# PA_LPF.net
KiCad netlist of a schematic drawn in Altium Designer
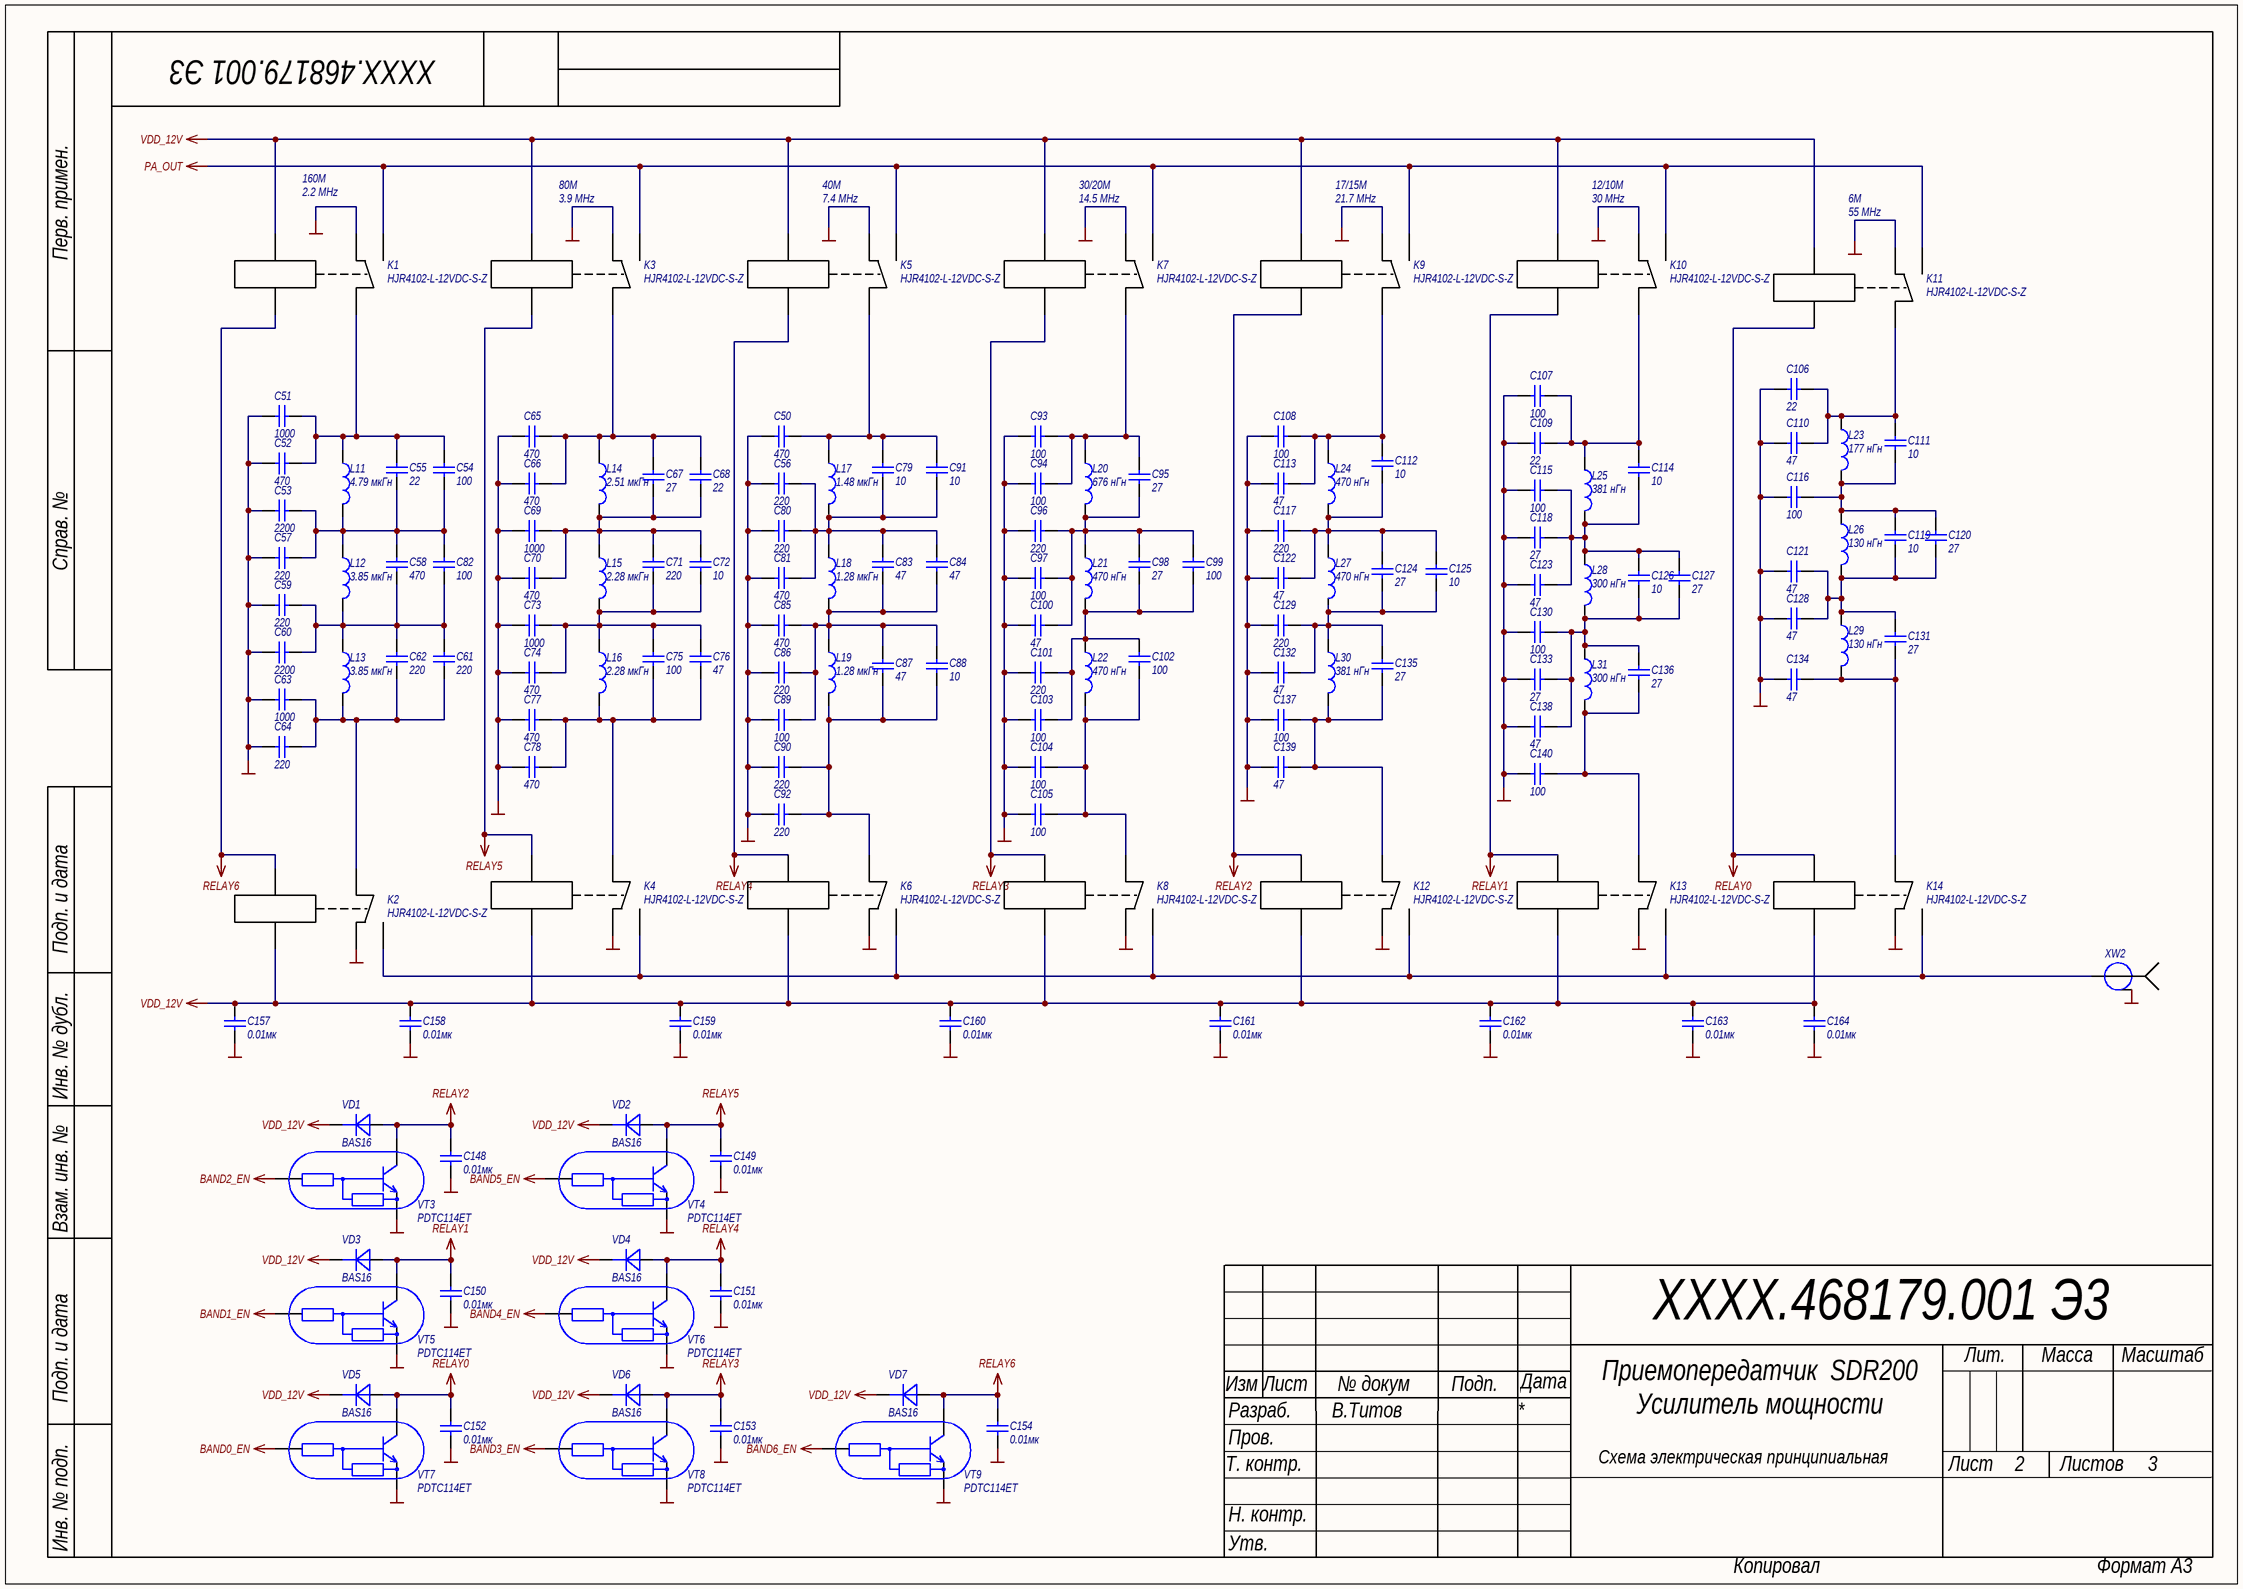
[diagram p0: PA_LPF.SchDoc]

(export (version "E")
  (design (tool "Eeschema 10.0.6"))
  (components
    (comp (ref "C50")
      (value "470")
      (footprint "CAPC3216X19L")
      (description "Кер. ЧИП-конденсатор")
      (fields (field (name "MANUFACTURER") "WALSIN") (field (name "TOLERANCE") "±10%"))
      (libsource (lib "nels_caps") (part "Кер.ЧИП конд. 1206 470пФ NP0 10% 2000В"))
    )
    (comp (ref "C51")
      (value "1000")
      (footprint "CAPC3216X19L")
      (description "Кер. ЧИП-конденсатор")
      (fields (field (name "MANUFACTURER") "Johanson") (field (name "TOLERANCE") "±10%"))
      (libsource (lib "nels_caps") (part "Кер.ЧИП конд. 1206 1000пФ X7К 10% 2000В"))
    )
    (comp (ref "C52")
      (value "470")
      (footprint "CAPC3216X19L")
      (description "Кер. ЧИП-конденсатор")
      (fields (field (name "MANUFACTURER") "WALSIN") (field (name "TOLERANCE") "±10%"))
      (libsource (lib "nels_caps") (part "Кер.ЧИП конд. 1206 470пФ NP0 10% 2000В"))
    )
    (comp (ref "C53")
      (value "2200")
      (footprint "CAPC3216X19L")
      (description "Кер. ЧИП-конденсатор")
      (fields (field (name "MANUFACTURER") "WALSIN") (field (name "TOLERANCE") "±10%"))
      (libsource (lib "nels_caps") (part "Кер.ЧИП конд. 1206 2200пФ X7К 10% 1000В"))
    )
    (comp (ref "C54")
      (value "100")
      (footprint "CAPC3216X19L")
      (description "Кер. ЧИП-конденсатор")
      (fields (field (name "MANUFACTURER") "WALSIN") (field (name "TOLERANCE") "±5%"))
      (libsource (lib "nels_caps") (part "Кер.ЧИП конд. 1206 100пФ NP0 5% 2000В"))
    )
    (comp (ref "C55")
      (value "22")
      (footprint "CAPC3216X19L")
      (description "Кер. ЧИП-конденсатор")
      (fields (field (name "MANUFACTURER") "WALSIN") (field (name "TOLERANCE") "±5%"))
      (libsource (lib "nels_caps") (part "Кер.ЧИП конд. 1206 22пФ NP0 5% 2000В"))
    )
    (comp (ref "C56")
      (value "220")
      (footprint "CAPC3216X19L")
      (description "Кер. ЧИП-конденсатор")
      (fields (field (name "MANUFACTURER") "Johanson") (field (name "TOLERANCE") "±10%"))
      (libsource (lib "nels_caps") (part "Кер.ЧИП конд. 1206 220пФ NP0 5% 2000В"))
    )
    (comp (ref "C57")
      (value "220")
      (footprint "CAPC3216X19L")
      (description "Кер. ЧИП-конденсатор")
      (fields (field (name "MANUFACTURER") "Johanson") (field (name "TOLERANCE") "±10%"))
      (libsource (lib "nels_caps") (part "Кер.ЧИП конд. 1206 220пФ NP0 5% 2000В"))
    )
    (comp (ref "C58")
      (value "470")
      (footprint "CAPC3216X19L")
      (description "Кер. ЧИП-конденсатор")
      (fields (field (name "MANUFACTURER") "WALSIN") (field (name "TOLERANCE") "±10%"))
      (libsource (lib "nels_caps") (part "Кер.ЧИП конд. 1206 470пФ NP0 10% 2000В"))
    )
    (comp (ref "C59")
      (value "220")
      (footprint "CAPC3216X19L")
      (description "Кер. ЧИП-конденсатор")
      (fields (field (name "MANUFACTURER") "Johanson") (field (name "TOLERANCE") "±10%"))
      (libsource (lib "nels_caps") (part "Кер.ЧИП конд. 1206 220пФ NP0 5% 2000В"))
    )
    (comp (ref "C60")
      (value "2200")
      (footprint "CAPC3216X19L")
      (description "Кер. ЧИП-конденсатор")
      (fields (field (name "MANUFACTURER") "WALSIN") (field (name "TOLERANCE") "±10%"))
      (libsource (lib "nels_caps") (part "Кер.ЧИП конд. 1206 2200пФ X7К 10% 1000В"))
    )
    (comp (ref "C61")
      (value "220")
      (footprint "CAPC3216X19L")
      (description "Кер. ЧИП-конденсатор")
      (fields (field (name "MANUFACTURER") "Johanson") (field (name "TOLERANCE") "±10%"))
      (libsource (lib "nels_caps") (part "Кер.ЧИП конд. 1206 220пФ NP0 5% 2000В"))
    )
    (comp (ref "C62")
      (value "220")
      (footprint "CAPC3216X19L")
      (description "Кер. ЧИП-конденсатор")
      (fields (field (name "MANUFACTURER") "Johanson") (field (name "TOLERANCE") "±10%"))
      (libsource (lib "nels_caps") (part "Кер.ЧИП конд. 1206 220пФ NP0 5% 2000В"))
    )
    (comp (ref "C63")
      (value "1000")
      (footprint "CAPC3216X19L")
      (description "Кер. ЧИП-конденсатор")
      (fields (field (name "MANUFACTURER") "Johanson") (field (name "TOLERANCE") "±10%"))
      (libsource (lib "nels_caps") (part "Кер.ЧИП конд. 1206 1000пФ X7К 10% 2000В"))
    )
    (comp (ref "C64")
      (value "220")
      (footprint "CAPC3216X19L")
      (description "Кер. ЧИП-конденсатор")
      (fields (field (name "MANUFACTURER") "Johanson") (field (name "TOLERANCE") "±10%"))
      (libsource (lib "nels_caps") (part "Кер.ЧИП конд. 1206 220пФ NP0 5% 2000В"))
    )
    (comp (ref "C65")
      (value "470")
      (footprint "CAPC3216X19L")
      (description "Кер. ЧИП-конденсатор")
      (fields (field (name "MANUFACTURER") "WALSIN") (field (name "TOLERANCE") "±10%"))
      (libsource (lib "nels_caps") (part "Кер.ЧИП конд. 1206 470пФ NP0 10% 2000В"))
    )
    (comp (ref "C66")
      (value "470")
      (footprint "CAPC3216X19L")
      (description "Кер. ЧИП-конденсатор")
      (fields (field (name "MANUFACTURER") "WALSIN") (field (name "TOLERANCE") "±10%"))
      (libsource (lib "nels_caps") (part "Кер.ЧИП конд. 1206 470пФ NP0 10% 2000В"))
    )
    (comp (ref "C67")
      (value "27")
      (footprint "CAPC3216X19L")
      (description "Кер. ЧИП-конденсатор")
      (fields (field (name "MANUFACTURER") "WALSIN") (field (name "TOLERANCE") "±10%"))
      (libsource (lib "nels_caps") (part "Кер.ЧИП конд. 1206 27пФ NP0 10% 2000В"))
    )
    (comp (ref "C68")
      (value "22")
      (footprint "CAPC3216X19L")
      (description "Кер. ЧИП-конденсатор")
      (fields (field (name "MANUFACTURER") "WALSIN") (field (name "TOLERANCE") "±5%"))
      (libsource (lib "nels_caps") (part "Кер.ЧИП конд. 1206 22пФ NP0 5% 2000В"))
    )
    (comp (ref "C69")
      (value "1000")
      (footprint "CAPC3216X19L")
      (description "Кер. ЧИП-конденсатор")
      (fields (field (name "MANUFACTURER") "Johanson") (field (name "TOLERANCE") "±10%"))
      (libsource (lib "nels_caps") (part "Кер.ЧИП конд. 1206 1000пФ X7К 10% 2000В"))
    )
    (comp (ref "C70")
      (value "470")
      (footprint "CAPC3216X19L")
      (description "Кер. ЧИП-конденсатор")
      (fields (field (name "MANUFACTURER") "WALSIN") (field (name "TOLERANCE") "±10%"))
      (libsource (lib "nels_caps") (part "Кер.ЧИП конд. 1206 470пФ NP0 10% 2000В"))
    )
    (comp (ref "C71")
      (value "220")
      (footprint "CAPC3216X19L")
      (description "Кер. ЧИП-конденсатор")
      (fields (field (name "MANUFACTURER") "Johanson") (field (name "TOLERANCE") "±10%"))
      (libsource (lib "nels_caps") (part "Кер.ЧИП конд. 1206 220пФ NP0 5% 2000В"))
    )
    (comp (ref "C72")
      (value "10")
      (footprint "CAPC3216X19L")
      (description "Кер. ЧИП-конденсатор")
      (fields (field (name "MANUFACTURER") "WALSIN") (field (name "TOLERANCE") "±5%"))
      (libsource (lib "nels_caps") (part "Кер.ЧИП конд. 1206 10пФ NP0 5% 2000В"))
    )
    (comp (ref "C73")
      (value "1000")
      (footprint "CAPC3216X19L")
      (description "Кер. ЧИП-конденсатор")
      (fields (field (name "MANUFACTURER") "Johanson") (field (name "TOLERANCE") "±10%"))
      (libsource (lib "nels_caps") (part "Кер.ЧИП конд. 1206 1000пФ X7К 10% 2000В"))
    )
    (comp (ref "C74")
      (value "470")
      (footprint "CAPC3216X19L")
      (description "Кер. ЧИП-конденсатор")
      (fields (field (name "MANUFACTURER") "WALSIN") (field (name "TOLERANCE") "±10%"))
      (libsource (lib "nels_caps") (part "Кер.ЧИП конд. 1206 470пФ NP0 10% 2000В"))
    )
    (comp (ref "C75")
      (value "100")
      (footprint "CAPC3216X19L")
      (description "Кер. ЧИП-конденсатор")
      (fields (field (name "MANUFACTURER") "WALSIN") (field (name "TOLERANCE") "±5%"))
      (libsource (lib "nels_caps") (part "Кер.ЧИП конд. 1206 100пФ NP0 5% 2000В"))
    )
    (comp (ref "C76")
      (value "47")
      (footprint "CAPC3216X19L")
      (description "Кер. ЧИП-конденсатор")
      (fields (field (name "MANUFACTURER") "WALSIN") (field (name "TOLERANCE") "±5%"))
      (libsource (lib "nels_caps") (part "Кер.ЧИП конд. 1206 47пФ NP0 5% 2000В"))
    )
    (comp (ref "C77")
      (value "470")
      (footprint "CAPC3216X19L")
      (description "Кер. ЧИП-конденсатор")
      (fields (field (name "MANUFACTURER") "WALSIN") (field (name "TOLERANCE") "±10%"))
      (libsource (lib "nels_caps") (part "Кер.ЧИП конд. 1206 470пФ NP0 10% 2000В"))
    )
    (comp (ref "C78")
      (value "470")
      (footprint "CAPC3216X19L")
      (description "Кер. ЧИП-конденсатор")
      (fields (field (name "MANUFACTURER") "WALSIN") (field (name "TOLERANCE") "±10%"))
      (libsource (lib "nels_caps") (part "Кер.ЧИП конд. 1206 470пФ NP0 10% 2000В"))
    )
    (comp (ref "C79")
      (value "10")
      (footprint "CAPC3216X19L")
      (description "Кер. ЧИП-конденсатор")
      (fields (field (name "MANUFACTURER") "WALSIN") (field (name "TOLERANCE") "±5%"))
      (libsource (lib "nels_caps") (part "Кер.ЧИП конд. 1206 10пФ NP0 5% 2000В"))
    )
    (comp (ref "C80")
      (value "220")
      (footprint "CAPC3216X19L")
      (description "Кер. ЧИП-конденсатор")
      (fields (field (name "MANUFACTURER") "Johanson") (field (name "TOLERANCE") "±10%"))
      (libsource (lib "nels_caps") (part "Кер.ЧИП конд. 1206 220пФ NP0 5% 2000В"))
    )
    (comp (ref "C81")
      (value "470")
      (footprint "CAPC3216X19L")
      (description "Кер. ЧИП-конденсатор")
      (fields (field (name "MANUFACTURER") "WALSIN") (field (name "TOLERANCE") "±10%"))
      (libsource (lib "nels_caps") (part "Кер.ЧИП конд. 1206 470пФ NP0 10% 2000В"))
    )
    (comp (ref "C82")
      (value "100")
      (footprint "CAPC3216X19L")
      (description "Кер. ЧИП-конденсатор")
      (fields (field (name "MANUFACTURER") "WALSIN") (field (name "TOLERANCE") "±5%"))
      (libsource (lib "nels_caps") (part "Кер.ЧИП конд. 1206 100пФ NP0 5% 2000В"))
    )
    (comp (ref "C83")
      (value "47")
      (footprint "CAPC3216X19L")
      (description "Кер. ЧИП-конденсатор")
      (fields (field (name "MANUFACTURER") "WALSIN") (field (name "TOLERANCE") "±5%"))
      (libsource (lib "nels_caps") (part "Кер.ЧИП конд. 1206 47пФ NP0 5% 2000В"))
    )
    (comp (ref "C84")
      (value "47")
      (footprint "CAPC3216X19L")
      (description "Кер. ЧИП-конденсатор")
      (fields (field (name "MANUFACTURER") "WALSIN") (field (name "TOLERANCE") "±5%"))
      (libsource (lib "nels_caps") (part "Кер.ЧИП конд. 1206 47пФ NP0 5% 2000В"))
    )
    (comp (ref "C85")
      (value "470")
      (footprint "CAPC3216X19L")
      (description "Кер. ЧИП-конденсатор")
      (fields (field (name "MANUFACTURER") "WALSIN") (field (name "TOLERANCE") "±10%"))
      (libsource (lib "nels_caps") (part "Кер.ЧИП конд. 1206 470пФ NP0 10% 2000В"))
    )
    (comp (ref "C86")
      (value "220")
      (footprint "CAPC3216X19L")
      (description "Кер. ЧИП-конденсатор")
      (fields (field (name "MANUFACTURER") "Johanson") (field (name "TOLERANCE") "±10%"))
      (libsource (lib "nels_caps") (part "Кер.ЧИП конд. 1206 220пФ NP0 5% 2000В"))
    )
    (comp (ref "C87")
      (value "47")
      (footprint "CAPC3216X19L")
      (description "Кер. ЧИП-конденсатор")
      (fields (field (name "MANUFACTURER") "WALSIN") (field (name "TOLERANCE") "±5%"))
      (libsource (lib "nels_caps") (part "Кер.ЧИП конд. 1206 47пФ NP0 5% 2000В"))
    )
    (comp (ref "C88")
      (value "10")
      (footprint "CAPC3216X19L")
      (description "Кер. ЧИП-конденсатор")
      (fields (field (name "MANUFACTURER") "WALSIN") (field (name "TOLERANCE") "±5%"))
      (libsource (lib "nels_caps") (part "Кер.ЧИП конд. 1206 10пФ NP0 5% 2000В"))
    )
    (comp (ref "C89")
      (value "100")
      (footprint "CAPC3216X19L")
      (description "Кер. ЧИП-конденсатор")
      (fields (field (name "MANUFACTURER") "WALSIN") (field (name "TOLERANCE") "±5%"))
      (libsource (lib "nels_caps") (part "Кер.ЧИП конд. 1206 100пФ NP0 5% 2000В"))
    )
    (comp (ref "C90")
      (value "220")
      (footprint "CAPC3216X19L")
      (description "Кер. ЧИП-конденсатор")
      (fields (field (name "MANUFACTURER") "Johanson") (field (name "TOLERANCE") "±10%"))
      (libsource (lib "nels_caps") (part "Кер.ЧИП конд. 1206 220пФ NP0 5% 2000В"))
    )
    (comp (ref "C91")
      (value "10")
      (footprint "CAPC3216X19L")
      (description "Кер. ЧИП-конденсатор")
      (fields (field (name "MANUFACTURER") "WALSIN") (field (name "TOLERANCE") "±5%"))
      (libsource (lib "nels_caps") (part "Кер.ЧИП конд. 1206 10пФ NP0 5% 2000В"))
    )
    (comp (ref "C92")
      (value "220")
      (footprint "CAPC3216X19L")
      (description "Кер. ЧИП-конденсатор")
      (fields (field (name "MANUFACTURER") "Johanson") (field (name "TOLERANCE") "±10%"))
      (libsource (lib "nels_caps") (part "Кер.ЧИП конд. 1206 220пФ NP0 5% 2000В"))
    )
    (comp (ref "C93")
      (value "100")
      (footprint "CAPC3216X19L")
      (description "Кер. ЧИП-конденсатор")
      (fields (field (name "MANUFACTURER") "WALSIN") (field (name "TOLERANCE") "±5%"))
      (libsource (lib "nels_caps") (part "Кер.ЧИП конд. 1206 100пФ NP0 5% 2000В"))
    )
    (comp (ref "C94")
      (value "100")
      (footprint "CAPC3216X19L")
      (description "Кер. ЧИП-конденсатор")
      (fields (field (name "MANUFACTURER") "WALSIN") (field (name "TOLERANCE") "±5%"))
      (libsource (lib "nels_caps") (part "Кер.ЧИП конд. 1206 100пФ NP0 5% 2000В"))
    )
    (comp (ref "C95")
      (value "27")
      (footprint "CAPC3216X19L")
      (description "Кер. ЧИП-конденсатор")
      (fields (field (name "MANUFACTURER") "WALSIN") (field (name "TOLERANCE") "±10%"))
      (libsource (lib "nels_caps") (part "Кер.ЧИП конд. 1206 27пФ NP0 10% 2000В"))
    )
    (comp (ref "C96")
      (value "220")
      (footprint "CAPC3216X19L")
      (description "Кер. ЧИП-конденсатор")
      (fields (field (name "MANUFACTURER") "Johanson") (field (name "TOLERANCE") "±10%"))
      (libsource (lib "nels_caps") (part "Кер.ЧИП конд. 1206 220пФ NP0 5% 2000В"))
    )
    (comp (ref "C97")
      (value "100")
      (footprint "CAPC3216X19L")
      (description "Кер. ЧИП-конденсатор")
      (fields (field (name "MANUFACTURER") "WALSIN") (field (name "TOLERANCE") "±5%"))
      (libsource (lib "nels_caps") (part "Кер.ЧИП конд. 1206 100пФ NP0 5% 2000В"))
    )
    (comp (ref "C98")
      (value "27")
      (footprint "CAPC3216X19L")
      (description "Кер. ЧИП-конденсатор")
      (fields (field (name "MANUFACTURER") "WALSIN") (field (name "TOLERANCE") "±10%"))
      (libsource (lib "nels_caps") (part "Кер.ЧИП конд. 1206 27пФ NP0 10% 2000В"))
    )
    (comp (ref "C99")
      (value "100")
      (footprint "CAPC3216X19L")
      (description "Кер. ЧИП-конденсатор")
      (fields (field (name "MANUFACTURER") "WALSIN") (field (name "TOLERANCE") "±5%"))
      (libsource (lib "nels_caps") (part "Кер.ЧИП конд. 1206 100пФ NP0 5% 2000В"))
    )
    (comp (ref "C100")
      (value "47")
      (footprint "CAPC3216X19L")
      (description "Кер. ЧИП-конденсатор")
      (fields (field (name "MANUFACTURER") "WALSIN") (field (name "TOLERANCE") "±5%"))
      (libsource (lib "nels_caps") (part "Кер.ЧИП конд. 1206 47пФ NP0 5% 2000В"))
    )
    (comp (ref "C101")
      (value "220")
      (footprint "CAPC3216X19L")
      (description "Кер. ЧИП-конденсатор")
      (fields (field (name "MANUFACTURER") "Johanson") (field (name "TOLERANCE") "±10%"))
      (libsource (lib "nels_caps") (part "Кер.ЧИП конд. 1206 220пФ NP0 5% 2000В"))
    )
    (comp (ref "C102")
      (value "100")
      (footprint "CAPC3216X19L")
      (description "Кер. ЧИП-конденсатор")
      (fields (field (name "MANUFACTURER") "WALSIN") (field (name "TOLERANCE") "±5%"))
      (libsource (lib "nels_caps") (part "Кер.ЧИП конд. 1206 100пФ NP0 5% 2000В"))
    )
    (comp (ref "C103")
      (value "100")
      (footprint "CAPC3216X19L")
      (description "Кер. ЧИП-конденсатор")
      (fields (field (name "MANUFACTURER") "WALSIN") (field (name "TOLERANCE") "±5%"))
      (libsource (lib "nels_caps") (part "Кер.ЧИП конд. 1206 100пФ NP0 5% 2000В"))
    )
    (comp (ref "C104")
      (value "100")
      (footprint "CAPC3216X19L")
      (description "Кер. ЧИП-конденсатор")
      (fields (field (name "MANUFACTURER") "WALSIN") (field (name "TOLERANCE") "±5%"))
      (libsource (lib "nels_caps") (part "Кер.ЧИП конд. 1206 100пФ NP0 5% 2000В"))
    )
    (comp (ref "C105")
      (value "100")
      (footprint "CAPC3216X19L")
      (description "Кер. ЧИП-конденсатор")
      (fields (field (name "MANUFACTURER") "WALSIN") (field (name "TOLERANCE") "±5%"))
      (libsource (lib "nels_caps") (part "Кер.ЧИП конд. 1206 100пФ NP0 5% 2000В"))
    )
    (comp (ref "C106")
      (value "22")
      (footprint "CAPC3216X19L")
      (description "Кер. ЧИП-конденсатор")
      (fields (field (name "MANUFACTURER") "WALSIN") (field (name "TOLERANCE") "±5%"))
      (libsource (lib "nels_caps") (part "Кер.ЧИП конд. 1206 22пФ NP0 5% 2000В"))
    )
    (comp (ref "C107")
      (value "100")
      (footprint "CAPC3216X19L")
      (description "Кер. ЧИП-конденсатор")
      (fields (field (name "MANUFACTURER") "WALSIN") (field (name "TOLERANCE") "±5%"))
      (libsource (lib "nels_caps") (part "Кер.ЧИП конд. 1206 100пФ NP0 5% 2000В"))
    )
    (comp (ref "C108")
      (value "100")
      (footprint "CAPC3216X19L")
      (description "Кер. ЧИП-конденсатор")
      (fields (field (name "MANUFACTURER") "WALSIN") (field (name "TOLERANCE") "±5%"))
      (libsource (lib "nels_caps") (part "Кер.ЧИП конд. 1206 100пФ NP0 5% 2000В"))
    )
    (comp (ref "C109")
      (value "22")
      (footprint "CAPC3216X19L")
      (description "Кер. ЧИП-конденсатор")
      (fields (field (name "MANUFACTURER") "WALSIN") (field (name "TOLERANCE") "±5%"))
      (libsource (lib "nels_caps") (part "Кер.ЧИП конд. 1206 22пФ NP0 5% 2000В"))
    )
    (comp (ref "C110")
      (value "47")
      (footprint "CAPC3216X19L")
      (description "Кер. ЧИП-конденсатор")
      (fields (field (name "MANUFACTURER") "WALSIN") (field (name "TOLERANCE") "±5%"))
      (libsource (lib "nels_caps") (part "Кер.ЧИП конд. 1206 47пФ NP0 5% 2000В"))
    )
    (comp (ref "C111")
      (value "10")
      (footprint "CAPC3216X19L")
      (description "Кер. ЧИП-конденсатор")
      (fields (field (name "MANUFACTURER") "WALSIN") (field (name "TOLERANCE") "±5%"))
      (libsource (lib "nels_caps") (part "Кер.ЧИП конд. 1206 10пФ NP0 5% 2000В"))
    )
    (comp (ref "C112")
      (value "10")
      (footprint "CAPC3216X19L")
      (description "Кер. ЧИП-конденсатор")
      (fields (field (name "MANUFACTURER") "WALSIN") (field (name "TOLERANCE") "±5%"))
      (libsource (lib "nels_caps") (part "Кер.ЧИП конд. 1206 10пФ NP0 5% 2000В"))
    )
    (comp (ref "C113")
      (value "47")
      (footprint "CAPC3216X19L")
      (description "Кер. ЧИП-конденсатор")
      (fields (field (name "MANUFACTURER") "WALSIN") (field (name "TOLERANCE") "±5%"))
      (libsource (lib "nels_caps") (part "Кер.ЧИП конд. 1206 47пФ NP0 5% 2000В"))
    )
    (comp (ref "C114")
      (value "10")
      (footprint "CAPC3216X19L")
      (description "Кер. ЧИП-конденсатор")
      (fields (field (name "MANUFACTURER") "WALSIN") (field (name "TOLERANCE") "±5%"))
      (libsource (lib "nels_caps") (part "Кер.ЧИП конд. 1206 10пФ NP0 5% 2000В"))
    )
    (comp (ref "C115")
      (value "100")
      (footprint "CAPC3216X19L")
      (description "Кер. ЧИП-конденсатор")
      (fields (field (name "MANUFACTURER") "WALSIN") (field (name "TOLERANCE") "±5%"))
      (libsource (lib "nels_caps") (part "Кер.ЧИП конд. 1206 100пФ NP0 5% 2000В"))
    )
    (comp (ref "C116")
      (value "100")
      (footprint "CAPC3216X19L")
      (description "Кер. ЧИП-конденсатор")
      (fields (field (name "MANUFACTURER") "WALSIN") (field (name "TOLERANCE") "±5%"))
      (libsource (lib "nels_caps") (part "Кер.ЧИП конд. 1206 100пФ NP0 5% 2000В"))
    )
    (comp (ref "C117")
      (value "220")
      (footprint "CAPC3216X19L")
      (description "Кер. ЧИП-конденсатор")
      (fields (field (name "MANUFACTURER") "Johanson") (field (name "TOLERANCE") "±10%"))
      (libsource (lib "nels_caps") (part "Кер.ЧИП конд. 1206 220пФ NP0 5% 2000В"))
    )
    (comp (ref "C118")
      (value "27")
      (footprint "CAPC3216X19L")
      (description "Кер. ЧИП-конденсатор")
      (fields (field (name "MANUFACTURER") "WALSIN") (field (name "TOLERANCE") "±10%"))
      (libsource (lib "nels_caps") (part "Кер.ЧИП конд. 1206 27пФ NP0 10% 2000В"))
    )
    (comp (ref "C119")
      (value "10")
      (footprint "CAPC3216X19L")
      (description "Кер. ЧИП-конденсатор")
      (fields (field (name "MANUFACTURER") "WALSIN") (field (name "TOLERANCE") "±5%"))
      (libsource (lib "nels_caps") (part "Кер.ЧИП конд. 1206 10пФ NP0 5% 2000В"))
    )
    (comp (ref "C120")
      (value "27")
      (footprint "CAPC3216X19L")
      (description "Кер. ЧИП-конденсатор")
      (fields (field (name "MANUFACTURER") "WALSIN") (field (name "TOLERANCE") "±10%"))
      (libsource (lib "nels_caps") (part "Кер.ЧИП конд. 1206 27пФ NP0 10% 2000В"))
    )
    (comp (ref "C121")
      (value "47")
      (footprint "CAPC3216X19L")
      (description "Кер. ЧИП-конденсатор")
      (fields (field (name "MANUFACTURER") "WALSIN") (field (name "TOLERANCE") "±5%"))
      (libsource (lib "nels_caps") (part "Кер.ЧИП конд. 1206 47пФ NP0 5% 2000В"))
    )
    (comp (ref "C122")
      (value "47")
      (footprint "CAPC3216X19L")
      (description "Кер. ЧИП-конденсатор")
      (fields (field (name "MANUFACTURER") "WALSIN") (field (name "TOLERANCE") "±5%"))
      (libsource (lib "nels_caps") (part "Кер.ЧИП конд. 1206 47пФ NP0 5% 2000В"))
    )
    (comp (ref "C123")
      (value "47")
      (footprint "CAPC3216X19L")
      (description "Кер. ЧИП-конденсатор")
      (fields (field (name "MANUFACTURER") "WALSIN") (field (name "TOLERANCE") "±5%"))
      (libsource (lib "nels_caps") (part "Кер.ЧИП конд. 1206 47пФ NP0 5% 2000В"))
    )
    (comp (ref "C124")
      (value "27")
      (footprint "CAPC3216X19L")
      (description "Кер. ЧИП-конденсатор")
      (fields (field (name "MANUFACTURER") "WALSIN") (field (name "TOLERANCE") "±10%"))
      (libsource (lib "nels_caps") (part "Кер.ЧИП конд. 1206 27пФ NP0 10% 2000В"))
    )
    (comp (ref "C125")
      (value "10")
      (footprint "CAPC3216X19L")
      (description "Кер. ЧИП-конденсатор")
      (fields (field (name "MANUFACTURER") "WALSIN") (field (name "TOLERANCE") "±5%"))
      (libsource (lib "nels_caps") (part "Кер.ЧИП конд. 1206 10пФ NP0 5% 2000В"))
    )
    (comp (ref "C126")
      (value "10")
      (footprint "CAPC3216X19L")
      (description "Кер. ЧИП-конденсатор")
      (fields (field (name "MANUFACTURER") "WALSIN") (field (name "TOLERANCE") "±5%"))
      (libsource (lib "nels_caps") (part "Кер.ЧИП конд. 1206 10пФ NP0 5% 2000В"))
    )
    (comp (ref "C127")
      (value "27")
      (footprint "CAPC3216X19L")
      (description "Кер. ЧИП-конденсатор")
      (fields (field (name "MANUFACTURER") "WALSIN") (field (name "TOLERANCE") "±10%"))
      (libsource (lib "nels_caps") (part "Кер.ЧИП конд. 1206 27пФ NP0 10% 2000В"))
    )
    (comp (ref "C128")
      (value "47")
      (footprint "CAPC3216X19L")
      (description "Кер. ЧИП-конденсатор")
      (fields (field (name "MANUFACTURER") "WALSIN") (field (name "TOLERANCE") "±5%"))
      (libsource (lib "nels_caps") (part "Кер.ЧИП конд. 1206 47пФ NP0 5% 2000В"))
    )
    (comp (ref "C129")
      (value "220")
      (footprint "CAPC3216X19L")
      (description "Кер. ЧИП-конденсатор")
      (fields (field (name "MANUFACTURER") "Johanson") (field (name "TOLERANCE") "±10%"))
      (libsource (lib "nels_caps") (part "Кер.ЧИП конд. 1206 220пФ NP0 5% 2000В"))
    )
    (comp (ref "C130")
      (value "100")
      (footprint "CAPC3216X19L")
      (description "Кер. ЧИП-конденсатор")
      (fields (field (name "MANUFACTURER") "WALSIN") (field (name "TOLERANCE") "±5%"))
      (libsource (lib "nels_caps") (part "Кер.ЧИП конд. 1206 100пФ NP0 5% 2000В"))
    )
    (comp (ref "C131")
      (value "27")
      (footprint "CAPC3216X19L")
      (description "Кер. ЧИП-конденсатор")
      (fields (field (name "MANUFACTURER") "WALSIN") (field (name "TOLERANCE") "±10%"))
      (libsource (lib "nels_caps") (part "Кер.ЧИП конд. 1206 27пФ NP0 10% 2000В"))
    )
    (comp (ref "C132")
      (value "47")
      (footprint "CAPC3216X19L")
      (description "Кер. ЧИП-конденсатор")
      (fields (field (name "MANUFACTURER") "WALSIN") (field (name "TOLERANCE") "±5%"))
      (libsource (lib "nels_caps") (part "Кер.ЧИП конд. 1206 47пФ NP0 5% 2000В"))
    )
    (comp (ref "C133")
      (value "27")
      (footprint "CAPC3216X19L")
      (description "Кер. ЧИП-конденсатор")
      (fields (field (name "MANUFACTURER") "WALSIN") (field (name "TOLERANCE") "±10%"))
      (libsource (lib "nels_caps") (part "Кер.ЧИП конд. 1206 27пФ NP0 10% 2000В"))
    )
    (comp (ref "C134")
      (value "47")
      (footprint "CAPC3216X19L")
      (description "Кер. ЧИП-конденсатор")
      (fields (field (name "MANUFACTURER") "WALSIN") (field (name "TOLERANCE") "±5%"))
      (libsource (lib "nels_caps") (part "Кер.ЧИП конд. 1206 47пФ NP0 5% 2000В"))
    )
    (comp (ref "C135")
      (value "27")
      (footprint "CAPC3216X19L")
      (description "Кер. ЧИП-конденсатор")
      (fields (field (name "MANUFACTURER") "WALSIN") (field (name "TOLERANCE") "±10%"))
      (libsource (lib "nels_caps") (part "Кер.ЧИП конд. 1206 27пФ NP0 10% 2000В"))
    )
    (comp (ref "C136")
      (value "27")
      (footprint "CAPC3216X19L")
      (description "Кер. ЧИП-конденсатор")
      (fields (field (name "MANUFACTURER") "WALSIN") (field (name "TOLERANCE") "±10%"))
      (libsource (lib "nels_caps") (part "Кер.ЧИП конд. 1206 27пФ NP0 10% 2000В"))
    )
    (comp (ref "C137")
      (value "100")
      (footprint "CAPC3216X19L")
      (description "Кер. ЧИП-конденсатор")
      (fields (field (name "MANUFACTURER") "WALSIN") (field (name "TOLERANCE") "±5%"))
      (libsource (lib "nels_caps") (part "Кер.ЧИП конд. 1206 100пФ NP0 5% 2000В"))
    )
    (comp (ref "C138")
      (value "47")
      (footprint "CAPC3216X19L")
      (description "Кер. ЧИП-конденсатор")
      (fields (field (name "MANUFACTURER") "WALSIN") (field (name "TOLERANCE") "±5%"))
      (libsource (lib "nels_caps") (part "Кер.ЧИП конд. 1206 47пФ NP0 5% 2000В"))
    )
    (comp (ref "C139")
      (value "47")
      (footprint "CAPC3216X19L")
      (description "Кер. ЧИП-конденсатор")
      (fields (field (name "MANUFACTURER") "WALSIN") (field (name "TOLERANCE") "±5%"))
      (libsource (lib "nels_caps") (part "Кер.ЧИП конд. 1206 47пФ NP0 5% 2000В"))
    )
    (comp (ref "C140")
      (value "100")
      (footprint "CAPC3216X19L")
      (description "Кер. ЧИП-конденсатор")
      (fields (field (name "MANUFACTURER") "WALSIN") (field (name "TOLERANCE") "±5%"))
      (libsource (lib "nels_caps") (part "Кер.ЧИП конд. 1206 100пФ NP0 5% 2000В"))
    )
    (comp (ref "C148")
      (value "0.01мк")
      (footprint "CAPC1005X06N")
      (description "Кер. ЧИП-конденсатор")
      (fields (field (name "TOLERANCE") "±20%"))
      (libsource (lib "nels_caps") (part "Кер.ЧИП конд. 0402 0.01мкФ X7R 10%, 50В"))
    )
    (comp (ref "C149")
      (value "0.01мк")
      (footprint "CAPC1005X06N")
      (description "Кер. ЧИП-конденсатор")
      (fields (field (name "TOLERANCE") "±20%"))
      (libsource (lib "nels_caps") (part "Кер.ЧИП конд. 0402 0.01мкФ X7R 10%, 50В"))
    )
    (comp (ref "C150")
      (value "0.01мк")
      (footprint "CAPC1005X06N")
      (description "Кер. ЧИП-конденсатор")
      (fields (field (name "TOLERANCE") "±20%"))
      (libsource (lib "nels_caps") (part "Кер.ЧИП конд. 0402 0.01мкФ X7R 10%, 50В"))
    )
    (comp (ref "C151")
      (value "0.01мк")
      (footprint "CAPC1005X06N")
      (description "Кер. ЧИП-конденсатор")
      (fields (field (name "TOLERANCE") "±20%"))
      (libsource (lib "nels_caps") (part "Кер.ЧИП конд. 0402 0.01мкФ X7R 10%, 50В"))
    )
    (comp (ref "C152")
      (value "0.01мк")
      (footprint "CAPC1005X06N")
      (description "Кер. ЧИП-конденсатор")
      (fields (field (name "TOLERANCE") "±20%"))
      (libsource (lib "nels_caps") (part "Кер.ЧИП конд. 0402 0.01мкФ X7R 10%, 50В"))
    )
    (comp (ref "C153")
      (value "0.01мк")
      (footprint "CAPC1005X06N")
      (description "Кер. ЧИП-конденсатор")
      (fields (field (name "TOLERANCE") "±20%"))
      (libsource (lib "nels_caps") (part "Кер.ЧИП конд. 0402 0.01мкФ X7R 10%, 50В"))
    )
    (comp (ref "C154")
      (value "0.01мк")
      (footprint "CAPC1005X06N")
      (description "Кер. ЧИП-конденсатор")
      (fields (field (name "TOLERANCE") "±20%"))
      (libsource (lib "nels_caps") (part "Кер.ЧИП конд. 0402 0.01мкФ X7R 10%, 50В"))
    )
    (comp (ref "C157")
      (value "0.01мк")
      (footprint "CAPC1005X06N")
      (description "Кер. ЧИП-конденсатор")
      (fields (field (name "TOLERANCE") "±20%"))
      (libsource (lib "nels_caps") (part "Кер.ЧИП конд. 0402 0.01мкФ X7R 10%, 50В"))
    )
    (comp (ref "C158")
      (value "0.01мк")
      (footprint "CAPC1005X06N")
      (description "Кер. ЧИП-конденсатор")
      (fields (field (name "TOLERANCE") "±20%"))
      (libsource (lib "nels_caps") (part "Кер.ЧИП конд. 0402 0.01мкФ X7R 10%, 50В"))
    )
    (comp (ref "C159")
      (value "0.01мк")
      (footprint "CAPC1005X06N")
      (description "Кер. ЧИП-конденсатор")
      (fields (field (name "TOLERANCE") "±20%"))
      (libsource (lib "nels_caps") (part "Кер.ЧИП конд. 0402 0.01мкФ X7R 10%, 50В"))
    )
    (comp (ref "C160")
      (value "0.01мк")
      (footprint "CAPC1005X06N")
      (description "Кер. ЧИП-конденсатор")
      (fields (field (name "TOLERANCE") "±20%"))
      (libsource (lib "nels_caps") (part "Кер.ЧИП конд. 0402 0.01мкФ X7R 10%, 50В"))
    )
    (comp (ref "C161")
      (value "0.01мк")
      (footprint "CAPC1005X06N")
      (description "Кер. ЧИП-конденсатор")
      (fields (field (name "TOLERANCE") "±20%"))
      (libsource (lib "nels_caps") (part "Кер.ЧИП конд. 0402 0.01мкФ X7R 10%, 50В"))
    )
    (comp (ref "C162")
      (value "0.01мк")
      (footprint "CAPC1005X06N")
      (description "Кер. ЧИП-конденсатор")
      (fields (field (name "TOLERANCE") "±20%"))
      (libsource (lib "nels_caps") (part "Кер.ЧИП конд. 0402 0.01мкФ X7R 10%, 50В"))
    )
    (comp (ref "C163")
      (value "0.01мк")
      (footprint "CAPC1005X06N")
      (description "Кер. ЧИП-конденсатор")
      (fields (field (name "TOLERANCE") "±20%"))
      (libsource (lib "nels_caps") (part "Кер.ЧИП конд. 0402 0.01мкФ X7R 10%, 50В"))
    )
    (comp (ref "C164")
      (value "0.01мк")
      (footprint "CAPC1005X06N")
      (description "Кер. ЧИП-конденсатор")
      (fields (field (name "TOLERANCE") "±20%"))
      (libsource (lib "nels_caps") (part "Кер.ЧИП конд. 0402 0.01мкФ X7R 10%, 50В"))
    )
    (comp (ref "K1")
      (value "HJR4102-L-12VDC-S-Z")
      (footprint "HJR4102")
      (description "Реле 1пер. 12VDC, 1A/240VAC")
      (libsource (lib "nels_other") (part "Реле HJR4102-L-12VDC-S-Z"))
    )
    (comp (ref "K2")
      (value "HJR4102-L-12VDC-S-Z")
      (footprint "HJR4102")
      (description "Реле 1пер. 12VDC, 1A/240VAC")
      (libsource (lib "nels_other") (part "Реле HJR4102-L-12VDC-S-Z"))
    )
    (comp (ref "K3")
      (value "HJR4102-L-12VDC-S-Z")
      (footprint "HJR4102")
      (description "Реле 1пер. 12VDC, 1A/240VAC")
      (libsource (lib "nels_other") (part "Реле HJR4102-L-12VDC-S-Z"))
    )
    (comp (ref "K4")
      (value "HJR4102-L-12VDC-S-Z")
      (footprint "HJR4102")
      (description "Реле 1пер. 12VDC, 1A/240VAC")
      (libsource (lib "nels_other") (part "Реле HJR4102-L-12VDC-S-Z"))
    )
    (comp (ref "K5")
      (value "HJR4102-L-12VDC-S-Z")
      (footprint "HJR4102")
      (description "Реле 1пер. 12VDC, 1A/240VAC")
      (libsource (lib "nels_other") (part "Реле HJR4102-L-12VDC-S-Z"))
    )
    (comp (ref "K6")
      (value "HJR4102-L-12VDC-S-Z")
      (footprint "HJR4102")
      (description "Реле 1пер. 12VDC, 1A/240VAC")
      (libsource (lib "nels_other") (part "Реле HJR4102-L-12VDC-S-Z"))
    )
    (comp (ref "K7")
      (value "HJR4102-L-12VDC-S-Z")
      (footprint "HJR4102")
      (description "Реле 1пер. 12VDC, 1A/240VAC")
      (libsource (lib "nels_other") (part "Реле HJR4102-L-12VDC-S-Z"))
    )
    (comp (ref "K8")
      (value "HJR4102-L-12VDC-S-Z")
      (footprint "HJR4102")
      (description "Реле 1пер. 12VDC, 1A/240VAC")
      (libsource (lib "nels_other") (part "Реле HJR4102-L-12VDC-S-Z"))
    )
    (comp (ref "K9")
      (value "HJR4102-L-12VDC-S-Z")
      (footprint "HJR4102")
      (description "Реле 1пер. 12VDC, 1A/240VAC")
      (libsource (lib "nels_other") (part "Реле HJR4102-L-12VDC-S-Z"))
    )
    (comp (ref "K10")
      (value "HJR4102-L-12VDC-S-Z")
      (footprint "HJR4102")
      (description "Реле 1пер. 12VDC, 1A/240VAC")
      (libsource (lib "nels_other") (part "Реле HJR4102-L-12VDC-S-Z"))
    )
    (comp (ref "K11")
      (value "HJR4102-L-12VDC-S-Z")
      (footprint "HJR4102")
      (description "Реле 1пер. 12VDC, 1A/240VAC")
      (libsource (lib "nels_other") (part "Реле HJR4102-L-12VDC-S-Z"))
    )
    (comp (ref "K12")
      (value "HJR4102-L-12VDC-S-Z")
      (footprint "HJR4102")
      (description "Реле 1пер. 12VDC, 1A/240VAC")
      (libsource (lib "nels_other") (part "Реле HJR4102-L-12VDC-S-Z"))
    )
    (comp (ref "K13")
      (value "HJR4102-L-12VDC-S-Z")
      (footprint "HJR4102")
      (description "Реле 1пер. 12VDC, 1A/240VAC")
      (libsource (lib "nels_other") (part "Реле HJR4102-L-12VDC-S-Z"))
    )
    (comp (ref "K14")
      (value "HJR4102-L-12VDC-S-Z")
      (footprint "HJR4102")
      (description "Реле 1пер. 12VDC, 1A/240VAC")
      (libsource (lib "nels_other") (part "Реле HJR4102-L-12VDC-S-Z"))
    )
    (comp (ref "L11")
      (value "4.79 мкГн")
      (footprint "T68-2")
      (description "29 витков")
      (libsource (lib "nels_ind") (part "Индуктивность T68-2 4.79 мкГн"))
    )
    (comp (ref "L12")
      (value "3.85 мкГн")
      (footprint "T68-2")
      (description "26 витков")
      (libsource (lib "nels_ind") (part "Индуктивность T68-2 3.85 мкГн"))
    )
    (comp (ref "L13")
      (value "3.85 мкГн")
      (footprint "T68-2")
      (description "26 витков")
      (libsource (lib "nels_ind") (part "Индуктивность T68-2 3.85 мкГн"))
    )
    (comp (ref "L14")
      (value "2.51 мкГн")
      (footprint "T68-2")
      (description "21 виток")
      (libsource (lib "nels_ind") (part "Индуктивность T68-2 2.51 мкГн"))
    )
    (comp (ref "L15")
      (value "2.28 мкГн")
      (footprint "T68-2")
      (libsource (lib "nels_ind") (part "Индуктивность T68-2 2.28 мкГн"))
    )
    (comp (ref "L16")
      (value "2.28 мкГн")
      (footprint "T68-2")
      (libsource (lib "nels_ind") (part "Индуктивность T68-2 2.28 мкГн"))
    )
    (comp (ref "L17")
      (value "1.48 мкГн")
      (footprint "T68-2")
      (description "16 витков")
      (libsource (lib "nels_ind") (part "Индуктивность T68-2 1.48 мкГн"))
    )
    (comp (ref "L18")
      (value "1.28 мкГн")
      (footprint "T68-2")
      (description "16 витков")
      (libsource (lib "nels_ind") (part "Индуктивность T68-2 1.28 мкГн"))
    )
    (comp (ref "L19")
      (value "1.28 мкГн")
      (footprint "T68-2")
      (description "16 витков")
      (libsource (lib "nels_ind") (part "Индуктивность T68-2 1.28 мкГн"))
    )
    (comp (ref "L20")
      (value "676 нГн")
      (footprint "T68-6")
      (description "12 витков")
      (libsource (lib "nels_ind") (part "Индуктивность T68-6 676 нГн"))
    )
    (comp (ref "L21")
      (value "470 нГн")
      (footprint "T68-6")
      (description "10 витков")
      (libsource (lib "nels_ind") (part "Индуктивность T68-6 470 нГн"))
    )
    (comp (ref "L22")
      (value "470 нГн")
      (footprint "T68-6")
      (description "10 витков")
      (libsource (lib "nels_ind") (part "Индуктивность T68-6 470 нГн"))
    )
    (comp (ref "L23")
      (value "177 нГн")
      (footprint "COIL D11 W4 L6")
      (description "4 витка, диаметр 11мм, длина 6мм")
      (libsource (lib "nels_ind") (part "Индуктивность 177 нГн"))
    )
    (comp (ref "L24")
      (value "470 нГн")
      (footprint "T68-6")
      (description "10 витков")
      (libsource (lib "nels_ind") (part "Индуктивность T68-6 470 нГн"))
    )
    (comp (ref "L25")
      (value "381 нГн")
      (footprint "T68-6")
      (description "9 витков")
      (libsource (lib "nels_ind") (part "Индуктивность T68-6 381 нГн"))
    )
    (comp (ref "L26")
      (value "130 нГн")
      (footprint "COIL D11 W4 L10")
      (description "4 витка, диаметр 11мм, длина 10мм")
      (libsource (lib "nels_ind") (part "Индуктивность 130 нГн"))
    )
    (comp (ref "L27")
      (value "470 нГн")
      (footprint "T68-6")
      (description "10 витков")
      (libsource (lib "nels_ind") (part "Индуктивность T68-6 470 нГн"))
    )
    (comp (ref "L28")
      (value "300 нГн")
      (footprint "T68-6")
      (description "8 витков")
      (libsource (lib "nels_ind") (part "Индуктивность T68-6 300 нГн"))
    )
    (comp (ref "L29")
      (value "130 нГн")
      (footprint "COIL D11 W4 L10")
      (description "4 витка, диаметр 11мм, длина 10мм")
      (libsource (lib "nels_ind") (part "Индуктивность 130 нГн"))
    )
    (comp (ref "L30")
      (value "381 нГн")
      (footprint "T68-6")
      (description "9 витков")
      (libsource (lib "nels_ind") (part "Индуктивность T68-6 381 нГн"))
    )
    (comp (ref "L31")
      (value "300 нГн")
      (footprint "T68-6")
      (description "8 витков")
      (libsource (lib "nels_ind") (part "Индуктивность T68-6 300 нГн"))
    )
    (comp (ref "VD1")
      (value "BAS16")
      (footprint "SOT23_N")
      (description "High-speed switching diodes")
      (fields (field (name "MANUFACTURER") "Nexperia"))
      (libsource (lib "nels_other") (part "ЧИП диод BAS16"))
    )
    (comp (ref "VD2")
      (value "BAS16")
      (footprint "SOT23_N")
      (description "High-speed switching diodes")
      (fields (field (name "MANUFACTURER") "Nexperia"))
      (libsource (lib "nels_other") (part "ЧИП диод BAS16"))
    )
    (comp (ref "VD3")
      (value "BAS16")
      (footprint "SOT23_N")
      (description "High-speed switching diodes")
      (fields (field (name "MANUFACTURER") "Nexperia"))
      (libsource (lib "nels_other") (part "ЧИП диод BAS16"))
    )
    (comp (ref "VD4")
      (value "BAS16")
      (footprint "SOT23_N")
      (description "High-speed switching diodes")
      (fields (field (name "MANUFACTURER") "Nexperia"))
      (libsource (lib "nels_other") (part "ЧИП диод BAS16"))
    )
    (comp (ref "VD5")
      (value "BAS16")
      (footprint "SOT23_N")
      (description "High-speed switching diodes")
      (fields (field (name "MANUFACTURER") "Nexperia"))
      (libsource (lib "nels_other") (part "ЧИП диод BAS16"))
    )
    (comp (ref "VD6")
      (value "BAS16")
      (footprint "SOT23_N")
      (description "High-speed switching diodes")
      (fields (field (name "MANUFACTURER") "Nexperia"))
      (libsource (lib "nels_other") (part "ЧИП диод BAS16"))
    )
    (comp (ref "VD7")
      (value "BAS16")
      (footprint "SOT23_N")
      (description "High-speed switching diodes")
      (fields (field (name "MANUFACTURER") "Nexperia"))
      (libsource (lib "nels_other") (part "ЧИП диод BAS16"))
    )
    (comp (ref "VT3")
      (value "PDTC114ET")
      (footprint "SOT23_N")
      (description "NPN resistor-equipped transistors;  R1 = 10 k, R2 = 10")
      (libsource (lib "nels_other") (part "ЧИП транзистор PDTC114ET"))
    )
    (comp (ref "VT4")
      (value "PDTC114ET")
      (footprint "SOT23_N")
      (description "NPN resistor-equipped transistors;  R1 = 10 k, R2 = 10")
      (libsource (lib "nels_other") (part "ЧИП транзистор PDTC114ET"))
    )
    (comp (ref "VT5")
      (value "PDTC114ET")
      (footprint "SOT23_N")
      (description "NPN resistor-equipped transistors;  R1 = 10 k, R2 = 10")
      (libsource (lib "nels_other") (part "ЧИП транзистор PDTC114ET"))
    )
    (comp (ref "VT6")
      (value "PDTC114ET")
      (footprint "SOT23_N")
      (description "NPN resistor-equipped transistors;  R1 = 10 k, R2 = 10")
      (libsource (lib "nels_other") (part "ЧИП транзистор PDTC114ET"))
    )
    (comp (ref "VT7")
      (value "PDTC114ET")
      (footprint "SOT23_N")
      (description "NPN resistor-equipped transistors;  R1 = 10 k, R2 = 10")
      (libsource (lib "nels_other") (part "ЧИП транзистор PDTC114ET"))
    )
    (comp (ref "VT8")
      (value "PDTC114ET")
      (footprint "SOT23_N")
      (description "NPN resistor-equipped transistors;  R1 = 10 k, R2 = 10")
      (libsource (lib "nels_other") (part "ЧИП транзистор PDTC114ET"))
    )
    (comp (ref "VT9")
      (value "PDTC114ET")
      (footprint "SOT23_N")
      (description "NPN resistor-equipped transistors;  R1 = 10 k, R2 = 10")
      (libsource (lib "nels_other") (part "ЧИП транзистор PDTC114ET"))
    )
    (comp (ref "XW2")
      (value "SMA-JR")
      (footprint "SMA-JR")
      (description "SMA-JR Разъем SMA гнездо на плату, прямой угол")
      (libsource (lib "nels_conn") (part "Соединитель коаксиальный SMA-JR"))
    )
  )
  (nets
    (net (code "1") (name "BAND0_EN") (class "Default")
      (node (ref "VT7") (pin "1") (pinfunction "B_1") (pintype "passive"))
    )
    (net (code "2") (name "BAND1_EN") (class "Default")
      (node (ref "VT5") (pin "1") (pinfunction "B_1") (pintype "passive"))
    )
    (net (code "3") (name "BAND2_EN") (class "Default")
      (node (ref "VT3") (pin "1") (pinfunction "B_1") (pintype "passive"))
    )
    (net (code "4") (name "BAND3_EN") (class "Default")
      (node (ref "VT8") (pin "1") (pinfunction "B_1") (pintype "passive"))
    )
    (net (code "5") (name "BAND4_EN") (class "Default")
      (node (ref "VT6") (pin "1") (pinfunction "B_1") (pintype "passive"))
    )
    (net (code "6") (name "BAND5_EN") (class "Default")
      (node (ref "VT4") (pin "1") (pinfunction "B_1") (pintype "passive"))
    )
    (net (code "7") (name "BAND6_EN") (class "Default")
      (node (ref "VT9") (pin "1") (pinfunction "B_1") (pintype "passive"))
    )
    (net (code "8") (name "GND") (class "Default")
      (node (ref "C100") (pin "2") (pinfunction "2_2") (pintype "passive"))
      (node (ref "C101") (pin "2") (pinfunction "2_2") (pintype "passive"))
      (node (ref "C103") (pin "2") (pinfunction "2_2") (pintype "passive"))
      (node (ref "C104") (pin "2") (pinfunction "2_2") (pintype "passive"))
      (node (ref "C105") (pin "2") (pinfunction "2_2") (pintype "passive"))
      (node (ref "C106") (pin "2") (pinfunction "2_2") (pintype "passive"))
      (node (ref "C107") (pin "2") (pinfunction "2_2") (pintype "passive"))
      (node (ref "C108") (pin "2") (pinfunction "2_2") (pintype "passive"))
      (node (ref "C109") (pin "2") (pinfunction "2_2") (pintype "passive"))
      (node (ref "C110") (pin "2") (pinfunction "2_2") (pintype "passive"))
      (node (ref "C113") (pin "2") (pinfunction "2_2") (pintype "passive"))
      (node (ref "C115") (pin "2") (pinfunction "2_2") (pintype "passive"))
      (node (ref "C116") (pin "2") (pinfunction "2_2") (pintype "passive"))
      (node (ref "C117") (pin "2") (pinfunction "2_2") (pintype "passive"))
      (node (ref "C118") (pin "2") (pinfunction "2_2") (pintype "passive"))
      (node (ref "C121") (pin "2") (pinfunction "2_2") (pintype "passive"))
      (node (ref "C122") (pin "2") (pinfunction "2_2") (pintype "passive"))
      (node (ref "C123") (pin "2") (pinfunction "2_2") (pintype "passive"))
      (node (ref "C128") (pin "2") (pinfunction "2_2") (pintype "passive"))
      (node (ref "C129") (pin "2") (pinfunction "2_2") (pintype "passive"))
      (node (ref "C130") (pin "2") (pinfunction "2_2") (pintype "passive"))
      (node (ref "C132") (pin "2") (pinfunction "2_2") (pintype "passive"))
      (node (ref "C133") (pin "2") (pinfunction "2_2") (pintype "passive"))
      (node (ref "C134") (pin "2") (pinfunction "2_2") (pintype "passive"))
      (node (ref "C137") (pin "2") (pinfunction "2_2") (pintype "passive"))
      (node (ref "C138") (pin "2") (pinfunction "2_2") (pintype "passive"))
      (node (ref "C139") (pin "2") (pinfunction "2_2") (pintype "passive"))
      (node (ref "C140") (pin "2") (pinfunction "2_2") (pintype "passive"))
      (node (ref "C148") (pin "1") (pinfunction "1_1") (pintype "passive"))
      (node (ref "C149") (pin "1") (pinfunction "1_1") (pintype "passive"))
      (node (ref "C150") (pin "1") (pinfunction "1_1") (pintype "passive"))
      (node (ref "C151") (pin "1") (pinfunction "1_1") (pintype "passive"))
      (node (ref "C152") (pin "1") (pinfunction "1_1") (pintype "passive"))
      (node (ref "C153") (pin "1") (pinfunction "1_1") (pintype "passive"))
      (node (ref "C154") (pin "1") (pinfunction "1_1") (pintype "passive"))
      (node (ref "C157") (pin "1") (pinfunction "1_1") (pintype "passive"))
      (node (ref "C158") (pin "1") (pinfunction "1_1") (pintype "passive"))
      (node (ref "C159") (pin "1") (pinfunction "1_1") (pintype "passive"))
      (node (ref "C160") (pin "1") (pinfunction "1_1") (pintype "passive"))
      (node (ref "C161") (pin "1") (pinfunction "1_1") (pintype "passive"))
      (node (ref "C162") (pin "1") (pinfunction "1_1") (pintype "passive"))
      (node (ref "C163") (pin "1") (pinfunction "1_1") (pintype "passive"))
      (node (ref "C164") (pin "1") (pinfunction "1_1") (pintype "passive"))
      (node (ref "C50") (pin "2") (pinfunction "2_2") (pintype "passive"))
      (node (ref "C51") (pin "2") (pinfunction "2_2") (pintype "passive"))
      (node (ref "C52") (pin "2") (pinfunction "2_2") (pintype "passive"))
      (node (ref "C53") (pin "2") (pinfunction "2_2") (pintype "passive"))
      (node (ref "C56") (pin "2") (pinfunction "2_2") (pintype "passive"))
      (node (ref "C57") (pin "2") (pinfunction "2_2") (pintype "passive"))
      (node (ref "C59") (pin "2") (pinfunction "2_2") (pintype "passive"))
      (node (ref "C60") (pin "2") (pinfunction "2_2") (pintype "passive"))
      (node (ref "C63") (pin "2") (pinfunction "2_2") (pintype "passive"))
      (node (ref "C64") (pin "2") (pinfunction "2_2") (pintype "passive"))
      (node (ref "C65") (pin "2") (pinfunction "2_2") (pintype "passive"))
      (node (ref "C66") (pin "2") (pinfunction "2_2") (pintype "passive"))
      (node (ref "C69") (pin "2") (pinfunction "2_2") (pintype "passive"))
      (node (ref "C70") (pin "2") (pinfunction "2_2") (pintype "passive"))
      (node (ref "C73") (pin "2") (pinfunction "2_2") (pintype "passive"))
      (node (ref "C74") (pin "2") (pinfunction "2_2") (pintype "passive"))
      (node (ref "C77") (pin "2") (pinfunction "2_2") (pintype "passive"))
      (node (ref "C78") (pin "2") (pinfunction "2_2") (pintype "passive"))
      (node (ref "C80") (pin "2") (pinfunction "2_2") (pintype "passive"))
      (node (ref "C81") (pin "2") (pinfunction "2_2") (pintype "passive"))
      (node (ref "C85") (pin "2") (pinfunction "2_2") (pintype "passive"))
      (node (ref "C86") (pin "2") (pinfunction "2_2") (pintype "passive"))
      (node (ref "C89") (pin "2") (pinfunction "2_2") (pintype "passive"))
      (node (ref "C90") (pin "2") (pinfunction "2_2") (pintype "passive"))
      (node (ref "C92") (pin "2") (pinfunction "2_2") (pintype "passive"))
      (node (ref "C93") (pin "2") (pinfunction "2_2") (pintype "passive"))
      (node (ref "C94") (pin "2") (pinfunction "2_2") (pintype "passive"))
      (node (ref "C96") (pin "2") (pinfunction "2_2") (pintype "passive"))
      (node (ref "C97") (pin "2") (pinfunction "2_2") (pintype "passive"))
      (node (ref "K1") (pin "7") (pintype "passive"))
      (node (ref "K10") (pin "7") (pintype "passive"))
      (node (ref "K11") (pin "7") (pintype "passive"))
      (node (ref "K12") (pin "7") (pintype "passive"))
      (node (ref "K13") (pin "7") (pintype "passive"))
      (node (ref "K14") (pin "7") (pintype "passive"))
      (node (ref "K2") (pin "7") (pintype "passive"))
      (node (ref "K3") (pin "7") (pintype "passive"))
      (node (ref "K4") (pin "7") (pintype "passive"))
      (node (ref "K5") (pin "7") (pintype "passive"))
      (node (ref "K6") (pin "7") (pintype "passive"))
      (node (ref "K7") (pin "7") (pintype "passive"))
      (node (ref "K8") (pin "7") (pintype "passive"))
      (node (ref "K9") (pin "7") (pintype "passive"))
      (node (ref "VT3") (pin "2") (pinfunction "E_2") (pintype "passive"))
      (node (ref "VT4") (pin "2") (pinfunction "E_2") (pintype "passive"))
      (node (ref "VT5") (pin "2") (pinfunction "E_2") (pintype "passive"))
      (node (ref "VT6") (pin "2") (pinfunction "E_2") (pintype "passive"))
      (node (ref "VT7") (pin "2") (pinfunction "E_2") (pintype "passive"))
      (node (ref "VT8") (pin "2") (pinfunction "E_2") (pintype "passive"))
      (node (ref "VT9") (pin "2") (pinfunction "E_2") (pintype "passive"))
      (node (ref "XW2") (pin "2") (pinfunction "2_2") (pintype "passive"))
    )
    (net (code "9") (name "Net-(C50-Pad1)") (class "Default")
      (node (ref "C50") (pin "1") (pinfunction "1_1") (pintype "passive"))
      (node (ref "C79") (pin "2") (pinfunction "2_2") (pintype "passive"))
      (node (ref "C91") (pin "2") (pinfunction "2_2") (pintype "passive"))
      (node (ref "K5") (pin "12") (pintype "passive"))
      (node (ref "L17") (pin "1") (pinfunction "1_1") (pintype "passive"))
    )
    (net (code "10") (name "Net-(C51-Pad1)") (class "Default")
      (node (ref "C51") (pin "1") (pinfunction "1_1") (pintype "passive"))
      (node (ref "C52") (pin "1") (pinfunction "1_1") (pintype "passive"))
      (node (ref "C54") (pin "2") (pinfunction "2_2") (pintype "passive"))
      (node (ref "C55") (pin "2") (pinfunction "2_2") (pintype "passive"))
      (node (ref "K1") (pin "12") (pintype "passive"))
      (node (ref "L11") (pin "1") (pinfunction "1_1") (pintype "passive"))
    )
    (net (code "11") (name "Net-(C53-Pad1)") (class "Default")
      (node (ref "C53") (pin "1") (pinfunction "1_1") (pintype "passive"))
      (node (ref "C54") (pin "1") (pinfunction "1_1") (pintype "passive"))
      (node (ref "C55") (pin "1") (pinfunction "1_1") (pintype "passive"))
      (node (ref "C57") (pin "1") (pinfunction "1_1") (pintype "passive"))
      (node (ref "C58") (pin "2") (pinfunction "2_2") (pintype "passive"))
      (node (ref "C82") (pin "2") (pinfunction "2_2") (pintype "passive"))
      (node (ref "L11") (pin "2") (pinfunction "2_2") (pintype "passive"))
      (node (ref "L12") (pin "1") (pinfunction "1_1") (pintype "passive"))
    )
    (net (code "12") (name "Net-(C56-Pad1)") (class "Default")
      (node (ref "C56") (pin "1") (pinfunction "1_1") (pintype "passive"))
      (node (ref "C79") (pin "1") (pinfunction "1_1") (pintype "passive"))
      (node (ref "C80") (pin "1") (pinfunction "1_1") (pintype "passive"))
      (node (ref "C81") (pin "1") (pinfunction "1_1") (pintype "passive"))
      (node (ref "C83") (pin "2") (pinfunction "2_2") (pintype "passive"))
      (node (ref "C84") (pin "2") (pinfunction "2_2") (pintype "passive"))
      (node (ref "C91") (pin "1") (pinfunction "1_1") (pintype "passive"))
      (node (ref "L17") (pin "2") (pinfunction "2_2") (pintype "passive"))
      (node (ref "L18") (pin "1") (pinfunction "1_1") (pintype "passive"))
    )
    (net (code "13") (name "Net-(C58-Pad1)") (class "Default")
      (node (ref "C58") (pin "1") (pinfunction "1_1") (pintype "passive"))
      (node (ref "C59") (pin "1") (pinfunction "1_1") (pintype "passive"))
      (node (ref "C60") (pin "1") (pinfunction "1_1") (pintype "passive"))
      (node (ref "C61") (pin "2") (pinfunction "2_2") (pintype "passive"))
      (node (ref "C62") (pin "2") (pinfunction "2_2") (pintype "passive"))
      (node (ref "C82") (pin "1") (pinfunction "1_1") (pintype "passive"))
      (node (ref "L12") (pin "2") (pinfunction "2_2") (pintype "passive"))
      (node (ref "L13") (pin "1") (pinfunction "1_1") (pintype "passive"))
    )
    (net (code "14") (name "Net-(C61-Pad1)") (class "Default")
      (node (ref "C61") (pin "1") (pinfunction "1_1") (pintype "passive"))
      (node (ref "C62") (pin "1") (pinfunction "1_1") (pintype "passive"))
      (node (ref "C63") (pin "1") (pinfunction "1_1") (pintype "passive"))
      (node (ref "C64") (pin "1") (pinfunction "1_1") (pintype "passive"))
      (node (ref "K2") (pin "12") (pintype "passive"))
      (node (ref "L13") (pin "2") (pinfunction "2_2") (pintype "passive"))
    )
    (net (code "15") (name "Net-(C65-Pad1)") (class "Default")
      (node (ref "C65") (pin "1") (pinfunction "1_1") (pintype "passive"))
      (node (ref "C66") (pin "1") (pinfunction "1_1") (pintype "passive"))
      (node (ref "C67") (pin "2") (pinfunction "2_2") (pintype "passive"))
      (node (ref "C68") (pin "2") (pinfunction "2_2") (pintype "passive"))
      (node (ref "K3") (pin "12") (pintype "passive"))
      (node (ref "L14") (pin "1") (pinfunction "1_1") (pintype "passive"))
    )
    (net (code "16") (name "Net-(C67-Pad1)") (class "Default")
      (node (ref "C67") (pin "1") (pinfunction "1_1") (pintype "passive"))
      (node (ref "C68") (pin "1") (pinfunction "1_1") (pintype "passive"))
      (node (ref "C69") (pin "1") (pinfunction "1_1") (pintype "passive"))
      (node (ref "C70") (pin "1") (pinfunction "1_1") (pintype "passive"))
      (node (ref "C71") (pin "1") (pinfunction "1_1") (pintype "passive"))
      (node (ref "C72") (pin "2") (pinfunction "2_2") (pintype "passive"))
      (node (ref "L14") (pin "2") (pinfunction "2_2") (pintype "passive"))
      (node (ref "L15") (pin "1") (pinfunction "1_1") (pintype "passive"))
    )
    (net (code "17") (name "Net-(C71-Pad2)") (class "Default")
      (node (ref "C71") (pin "2") (pinfunction "2_2") (pintype "passive"))
      (node (ref "C72") (pin "1") (pinfunction "1_1") (pintype "passive"))
      (node (ref "C73") (pin "1") (pinfunction "1_1") (pintype "passive"))
      (node (ref "C74") (pin "1") (pinfunction "1_1") (pintype "passive"))
      (node (ref "C75") (pin "2") (pinfunction "2_2") (pintype "passive"))
      (node (ref "C76") (pin "2") (pinfunction "2_2") (pintype "passive"))
      (node (ref "L15") (pin "2") (pinfunction "2_2") (pintype "passive"))
      (node (ref "L16") (pin "1") (pinfunction "1_1") (pintype "passive"))
    )
    (net (code "18") (name "Net-(C75-Pad1)") (class "Default")
      (node (ref "C75") (pin "1") (pinfunction "1_1") (pintype "passive"))
      (node (ref "C76") (pin "1") (pinfunction "1_1") (pintype "passive"))
      (node (ref "C77") (pin "1") (pinfunction "1_1") (pintype "passive"))
      (node (ref "C78") (pin "1") (pinfunction "1_1") (pintype "passive"))
      (node (ref "K4") (pin "12") (pintype "passive"))
      (node (ref "L16") (pin "2") (pinfunction "2_2") (pintype "passive"))
    )
    (net (code "19") (name "Net-(C83-Pad1)") (class "Default")
      (node (ref "C83") (pin "1") (pinfunction "1_1") (pintype "passive"))
      (node (ref "C84") (pin "1") (pinfunction "1_1") (pintype "passive"))
      (node (ref "C85") (pin "1") (pinfunction "1_1") (pintype "passive"))
      (node (ref "C86") (pin "1") (pinfunction "1_1") (pintype "passive"))
      (node (ref "C87") (pin "2") (pinfunction "2_2") (pintype "passive"))
      (node (ref "C88") (pin "2") (pinfunction "2_2") (pintype "passive"))
      (node (ref "C89") (pin "1") (pinfunction "1_1") (pintype "passive"))
      (node (ref "L18") (pin "2") (pinfunction "2_2") (pintype "passive"))
      (node (ref "L19") (pin "1") (pinfunction "1_1") (pintype "passive"))
    )
    (net (code "20") (name "Net-(C87-Pad1)") (class "Default")
      (node (ref "C87") (pin "1") (pinfunction "1_1") (pintype "passive"))
      (node (ref "C88") (pin "1") (pinfunction "1_1") (pintype "passive"))
      (node (ref "C90") (pin "1") (pinfunction "1_1") (pintype "passive"))
      (node (ref "C92") (pin "1") (pinfunction "1_1") (pintype "passive"))
      (node (ref "K6") (pin "12") (pintype "passive"))
      (node (ref "L19") (pin "2") (pinfunction "2_2") (pintype "passive"))
    )
    (net (code "21") (name "Net-(C93-Pad1)") (class "Default")
      (node (ref "C93") (pin "1") (pinfunction "1_1") (pintype "passive"))
      (node (ref "C94") (pin "1") (pinfunction "1_1") (pintype "passive"))
      (node (ref "C95") (pin "2") (pinfunction "2_2") (pintype "passive"))
      (node (ref "K7") (pin "12") (pintype "passive"))
      (node (ref "L20") (pin "1") (pinfunction "1_1") (pintype "passive"))
    )
    (net (code "22") (name "Net-(C100-Pad1)") (class "Default")
      (node (ref "C100") (pin "1") (pinfunction "1_1") (pintype "passive"))
      (node (ref "C95") (pin "1") (pinfunction "1_1") (pintype "passive"))
      (node (ref "C96") (pin "1") (pinfunction "1_1") (pintype "passive"))
      (node (ref "C97") (pin "1") (pinfunction "1_1") (pintype "passive"))
      (node (ref "C98") (pin "2") (pinfunction "2_2") (pintype "passive"))
      (node (ref "C99") (pin "2") (pinfunction "2_2") (pintype "passive"))
      (node (ref "L20") (pin "2") (pinfunction "2_2") (pintype "passive"))
      (node (ref "L21") (pin "1") (pinfunction "1_1") (pintype "passive"))
    )
    (net (code "23") (name "Net-(C101-Pad1)") (class "Default")
      (node (ref "C101") (pin "1") (pinfunction "1_1") (pintype "passive"))
      (node (ref "C102") (pin "2") (pinfunction "2_2") (pintype "passive"))
      (node (ref "C103") (pin "1") (pinfunction "1_1") (pintype "passive"))
      (node (ref "C98") (pin "1") (pinfunction "1_1") (pintype "passive"))
      (node (ref "C99") (pin "1") (pinfunction "1_1") (pintype "passive"))
      (node (ref "L21") (pin "2") (pinfunction "2_2") (pintype "passive"))
      (node (ref "L22") (pin "1") (pinfunction "1_1") (pintype "passive"))
    )
    (net (code "24") (name "Net-(C102-Pad1)") (class "Default")
      (node (ref "C102") (pin "1") (pinfunction "1_1") (pintype "passive"))
      (node (ref "C104") (pin "1") (pinfunction "1_1") (pintype "passive"))
      (node (ref "C105") (pin "1") (pinfunction "1_1") (pintype "passive"))
      (node (ref "K8") (pin "12") (pintype "passive"))
      (node (ref "L22") (pin "2") (pinfunction "2_2") (pintype "passive"))
    )
    (net (code "25") (name "Net-(C106-Pad1)") (class "Default")
      (node (ref "C106") (pin "1") (pinfunction "1_1") (pintype "passive"))
      (node (ref "C110") (pin "1") (pinfunction "1_1") (pintype "passive"))
      (node (ref "C111") (pin "2") (pinfunction "2_2") (pintype "passive"))
      (node (ref "K11") (pin "12") (pintype "passive"))
      (node (ref "L23") (pin "1") (pinfunction "1_1") (pintype "passive"))
    )
    (net (code "26") (name "Net-(C107-Pad1)") (class "Default")
      (node (ref "C107") (pin "1") (pinfunction "1_1") (pintype "passive"))
      (node (ref "C109") (pin "1") (pinfunction "1_1") (pintype "passive"))
      (node (ref "C114") (pin "2") (pinfunction "2_2") (pintype "passive"))
      (node (ref "K10") (pin "12") (pintype "passive"))
      (node (ref "L25") (pin "1") (pinfunction "1_1") (pintype "passive"))
    )
    (net (code "27") (name "Net-(C108-Pad1)") (class "Default")
      (node (ref "C108") (pin "1") (pinfunction "1_1") (pintype "passive"))
      (node (ref "C112") (pin "2") (pinfunction "2_2") (pintype "passive"))
      (node (ref "C113") (pin "1") (pinfunction "1_1") (pintype "passive"))
      (node (ref "K9") (pin "12") (pintype "passive"))
      (node (ref "L24") (pin "1") (pinfunction "1_1") (pintype "passive"))
    )
    (net (code "28") (name "Net-(C111-Pad1)") (class "Default")
      (node (ref "C111") (pin "1") (pinfunction "1_1") (pintype "passive"))
      (node (ref "C116") (pin "1") (pinfunction "1_1") (pintype "passive"))
      (node (ref "C119") (pin "2") (pinfunction "2_2") (pintype "passive"))
      (node (ref "C120") (pin "2") (pinfunction "2_2") (pintype "passive"))
      (node (ref "L23") (pin "2") (pinfunction "2_2") (pintype "passive"))
      (node (ref "L26") (pin "1") (pinfunction "1_1") (pintype "passive"))
    )
    (net (code "29") (name "Net-(C112-Pad1)") (class "Default")
      (node (ref "C112") (pin "1") (pinfunction "1_1") (pintype "passive"))
      (node (ref "C117") (pin "1") (pinfunction "1_1") (pintype "passive"))
      (node (ref "C122") (pin "1") (pinfunction "1_1") (pintype "passive"))
      (node (ref "C124") (pin "2") (pinfunction "2_2") (pintype "passive"))
      (node (ref "C125") (pin "2") (pinfunction "2_2") (pintype "passive"))
      (node (ref "L24") (pin "2") (pinfunction "2_2") (pintype "passive"))
      (node (ref "L27") (pin "1") (pinfunction "1_1") (pintype "passive"))
    )
    (net (code "30") (name "Net-(C114-Pad1)") (class "Default")
      (node (ref "C114") (pin "1") (pinfunction "1_1") (pintype "passive"))
      (node (ref "C115") (pin "1") (pinfunction "1_1") (pintype "passive"))
      (node (ref "C118") (pin "1") (pinfunction "1_1") (pintype "passive"))
      (node (ref "C123") (pin "1") (pinfunction "1_1") (pintype "passive"))
      (node (ref "C126") (pin "2") (pinfunction "2_2") (pintype "passive"))
      (node (ref "C127") (pin "2") (pinfunction "2_2") (pintype "passive"))
      (node (ref "L25") (pin "2") (pinfunction "2_2") (pintype "passive"))
      (node (ref "L28") (pin "1") (pinfunction "1_1") (pintype "passive"))
    )
    (net (code "31") (name "Net-(C119-Pad1)") (class "Default")
      (node (ref "C119") (pin "1") (pinfunction "1_1") (pintype "passive"))
      (node (ref "C120") (pin "1") (pinfunction "1_1") (pintype "passive"))
      (node (ref "C121") (pin "1") (pinfunction "1_1") (pintype "passive"))
      (node (ref "C128") (pin "1") (pinfunction "1_1") (pintype "passive"))
      (node (ref "C131") (pin "2") (pinfunction "2_2") (pintype "passive"))
      (node (ref "L26") (pin "2") (pinfunction "2_2") (pintype "passive"))
      (node (ref "L29") (pin "1") (pinfunction "1_1") (pintype "passive"))
    )
    (net (code "32") (name "Net-(C124-Pad1)") (class "Default")
      (node (ref "C124") (pin "1") (pinfunction "1_1") (pintype "passive"))
      (node (ref "C125") (pin "1") (pinfunction "1_1") (pintype "passive"))
      (node (ref "C129") (pin "1") (pinfunction "1_1") (pintype "passive"))
      (node (ref "C132") (pin "1") (pinfunction "1_1") (pintype "passive"))
      (node (ref "C135") (pin "2") (pinfunction "2_2") (pintype "passive"))
      (node (ref "L27") (pin "2") (pinfunction "2_2") (pintype "passive"))
      (node (ref "L30") (pin "1") (pinfunction "1_1") (pintype "passive"))
    )
    (net (code "33") (name "Net-(C126-Pad1)") (class "Default")
      (node (ref "C126") (pin "1") (pinfunction "1_1") (pintype "passive"))
      (node (ref "C127") (pin "1") (pinfunction "1_1") (pintype "passive"))
      (node (ref "C130") (pin "1") (pinfunction "1_1") (pintype "passive"))
      (node (ref "C133") (pin "1") (pinfunction "1_1") (pintype "passive"))
      (node (ref "C136") (pin "2") (pinfunction "2_2") (pintype "passive"))
      (node (ref "C138") (pin "1") (pinfunction "1_1") (pintype "passive"))
      (node (ref "L28") (pin "2") (pinfunction "2_2") (pintype "passive"))
      (node (ref "L31") (pin "1") (pinfunction "1_1") (pintype "passive"))
    )
    (net (code "34") (name "Net-(C131-Pad1)") (class "Default")
      (node (ref "C131") (pin "1") (pinfunction "1_1") (pintype "passive"))
      (node (ref "C134") (pin "1") (pinfunction "1_1") (pintype "passive"))
      (node (ref "K14") (pin "12") (pintype "passive"))
      (node (ref "L29") (pin "2") (pinfunction "2_2") (pintype "passive"))
    )
    (net (code "35") (name "Net-(C135-Pad1)") (class "Default")
      (node (ref "C135") (pin "1") (pinfunction "1_1") (pintype "passive"))
      (node (ref "C137") (pin "1") (pinfunction "1_1") (pintype "passive"))
      (node (ref "C139") (pin "1") (pinfunction "1_1") (pintype "passive"))
      (node (ref "K12") (pin "12") (pintype "passive"))
      (node (ref "L30") (pin "2") (pinfunction "2_2") (pintype "passive"))
    )
    (net (code "36") (name "Net-(C136-Pad1)") (class "Default")
      (node (ref "C136") (pin "1") (pinfunction "1_1") (pintype "passive"))
      (node (ref "C140") (pin "1") (pinfunction "1_1") (pintype "passive"))
      (node (ref "K13") (pin "12") (pintype "passive"))
      (node (ref "L31") (pin "2") (pinfunction "2_2") (pintype "passive"))
    )
    (net (code "37") (name "Net-(K12-Pad6)") (class "Default")
      (node (ref "K12") (pin "6") (pintype "passive"))
      (node (ref "K13") (pin "6") (pintype "passive"))
      (node (ref "K14") (pin "6") (pintype "passive"))
      (node (ref "K2") (pin "6") (pintype "passive"))
      (node (ref "K4") (pin "6") (pintype "passive"))
      (node (ref "K6") (pin "6") (pintype "passive"))
      (node (ref "K8") (pin "6") (pintype "passive"))
      (node (ref "XW2") (pin "1") (pinfunction "1_1") (pintype "passive"))
    )
    (net (code "38") (name "PA_OUT") (class "Default")
      (node (ref "K1") (pin "6") (pintype "passive"))
      (node (ref "K10") (pin "6") (pintype "passive"))
      (node (ref "K11") (pin "6") (pintype "passive"))
      (node (ref "K3") (pin "6") (pintype "passive"))
      (node (ref "K5") (pin "6") (pintype "passive"))
      (node (ref "K7") (pin "6") (pintype "passive"))
      (node (ref "K9") (pin "6") (pintype "passive"))
    )
    (net (code "39") (name "RELAY0") (class "Default")
      (node (ref "C152") (pin "2") (pinfunction "2_2") (pintype "passive"))
      (node (ref "K11") (pin "5") (pintype "passive"))
      (node (ref "K14") (pin "5") (pintype "passive"))
      (node (ref "VD5") (pin "1") (pinfunction "A_1") (pintype "passive"))
      (node (ref "VT7") (pin "3") (pinfunction "C_3") (pintype "passive"))
    )
    (net (code "40") (name "RELAY1") (class "Default")
      (node (ref "C150") (pin "2") (pinfunction "2_2") (pintype "passive"))
      (node (ref "K10") (pin "5") (pintype "passive"))
      (node (ref "K13") (pin "5") (pintype "passive"))
      (node (ref "VD3") (pin "1") (pinfunction "A_1") (pintype "passive"))
      (node (ref "VT5") (pin "3") (pinfunction "C_3") (pintype "passive"))
    )
    (net (code "41") (name "RELAY2") (class "Default")
      (node (ref "C148") (pin "2") (pinfunction "2_2") (pintype "passive"))
      (node (ref "K12") (pin "5") (pintype "passive"))
      (node (ref "K9") (pin "5") (pintype "passive"))
      (node (ref "VD1") (pin "1") (pinfunction "A_1") (pintype "passive"))
      (node (ref "VT3") (pin "3") (pinfunction "C_3") (pintype "passive"))
    )
    (net (code "42") (name "RELAY3") (class "Default")
      (node (ref "C153") (pin "2") (pinfunction "2_2") (pintype "passive"))
      (node (ref "K7") (pin "5") (pintype "passive"))
      (node (ref "K8") (pin "5") (pintype "passive"))
      (node (ref "VD6") (pin "1") (pinfunction "A_1") (pintype "passive"))
      (node (ref "VT8") (pin "3") (pinfunction "C_3") (pintype "passive"))
    )
    (net (code "43") (name "RELAY4") (class "Default")
      (node (ref "C151") (pin "2") (pinfunction "2_2") (pintype "passive"))
      (node (ref "K5") (pin "5") (pintype "passive"))
      (node (ref "K6") (pin "5") (pintype "passive"))
      (node (ref "VD4") (pin "1") (pinfunction "A_1") (pintype "passive"))
      (node (ref "VT6") (pin "3") (pinfunction "C_3") (pintype "passive"))
    )
    (net (code "44") (name "RELAY5") (class "Default")
      (node (ref "C149") (pin "2") (pinfunction "2_2") (pintype "passive"))
      (node (ref "K3") (pin "5") (pintype "passive"))
      (node (ref "K4") (pin "5") (pintype "passive"))
      (node (ref "VD2") (pin "1") (pinfunction "A_1") (pintype "passive"))
      (node (ref "VT4") (pin "3") (pinfunction "C_3") (pintype "passive"))
    )
    (net (code "45") (name "RELAY6") (class "Default")
      (node (ref "C154") (pin "2") (pinfunction "2_2") (pintype "passive"))
      (node (ref "K1") (pin "5") (pintype "passive"))
      (node (ref "K2") (pin "5") (pintype "passive"))
      (node (ref "VD7") (pin "1") (pinfunction "A_1") (pintype "passive"))
      (node (ref "VT9") (pin "3") (pinfunction "C_3") (pintype "passive"))
    )
    (net (code "46") (name "VDD_12V") (class "Default")
      (node (ref "C157") (pin "2") (pinfunction "2_2") (pintype "passive"))
      (node (ref "C158") (pin "2") (pinfunction "2_2") (pintype "passive"))
      (node (ref "C159") (pin "2") (pinfunction "2_2") (pintype "passive"))
      (node (ref "C160") (pin "2") (pinfunction "2_2") (pintype "passive"))
      (node (ref "C161") (pin "2") (pinfunction "2_2") (pintype "passive"))
      (node (ref "C162") (pin "2") (pinfunction "2_2") (pintype "passive"))
      (node (ref "C163") (pin "2") (pinfunction "2_2") (pintype "passive"))
      (node (ref "C164") (pin "2") (pinfunction "2_2") (pintype "passive"))
      (node (ref "K1") (pin "8") (pintype "passive"))
      (node (ref "K10") (pin "8") (pintype "passive"))
      (node (ref "K11") (pin "8") (pintype "passive"))
      (node (ref "K12") (pin "8") (pintype "passive"))
      (node (ref "K13") (pin "8") (pintype "passive"))
      (node (ref "K14") (pin "8") (pintype "passive"))
      (node (ref "K2") (pin "8") (pintype "passive"))
      (node (ref "K3") (pin "8") (pintype "passive"))
      (node (ref "K4") (pin "8") (pintype "passive"))
      (node (ref "K5") (pin "8") (pintype "passive"))
      (node (ref "K6") (pin "8") (pintype "passive"))
      (node (ref "K7") (pin "8") (pintype "passive"))
      (node (ref "K8") (pin "8") (pintype "passive"))
      (node (ref "K9") (pin "8") (pintype "passive"))
      (node (ref "VD1") (pin "3") (pinfunction "K_3") (pintype "passive"))
      (node (ref "VD2") (pin "3") (pinfunction "K_3") (pintype "passive"))
      (node (ref "VD3") (pin "3") (pinfunction "K_3") (pintype "passive"))
      (node (ref "VD4") (pin "3") (pinfunction "K_3") (pintype "passive"))
      (node (ref "VD5") (pin "3") (pinfunction "K_3") (pintype "passive"))
      (node (ref "VD6") (pin "3") (pinfunction "K_3") (pintype "passive"))
      (node (ref "VD7") (pin "3") (pinfunction "K_3") (pintype "passive"))
    )
  )
)
